# 101_GridPosMainHub.net
KiCad netlist of a schematic drawn in Altium Designer
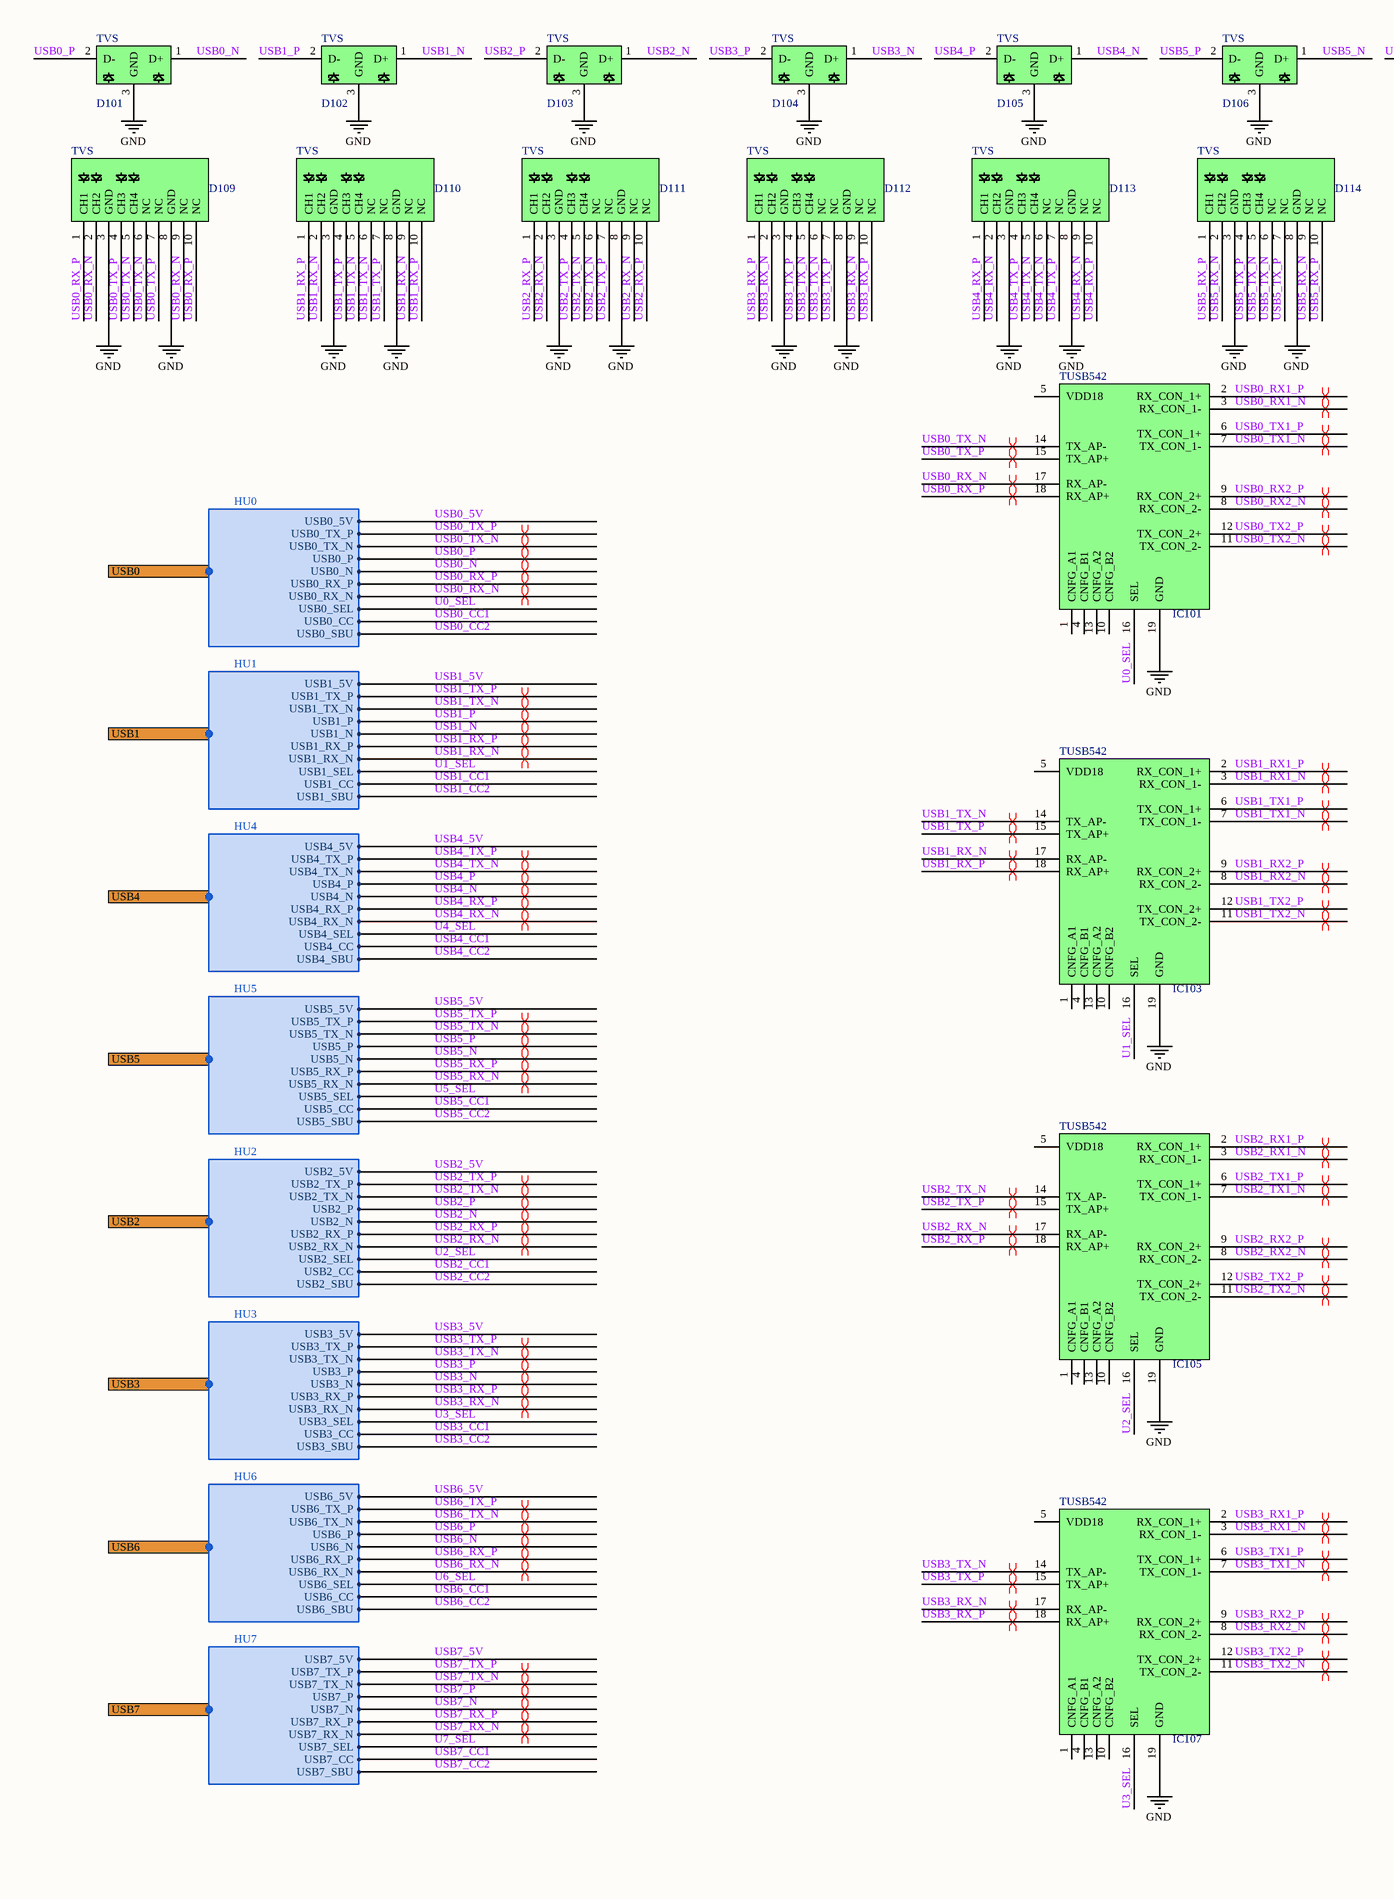
[diagram p0: 101_GridPosMainHub.SchDoc, left]
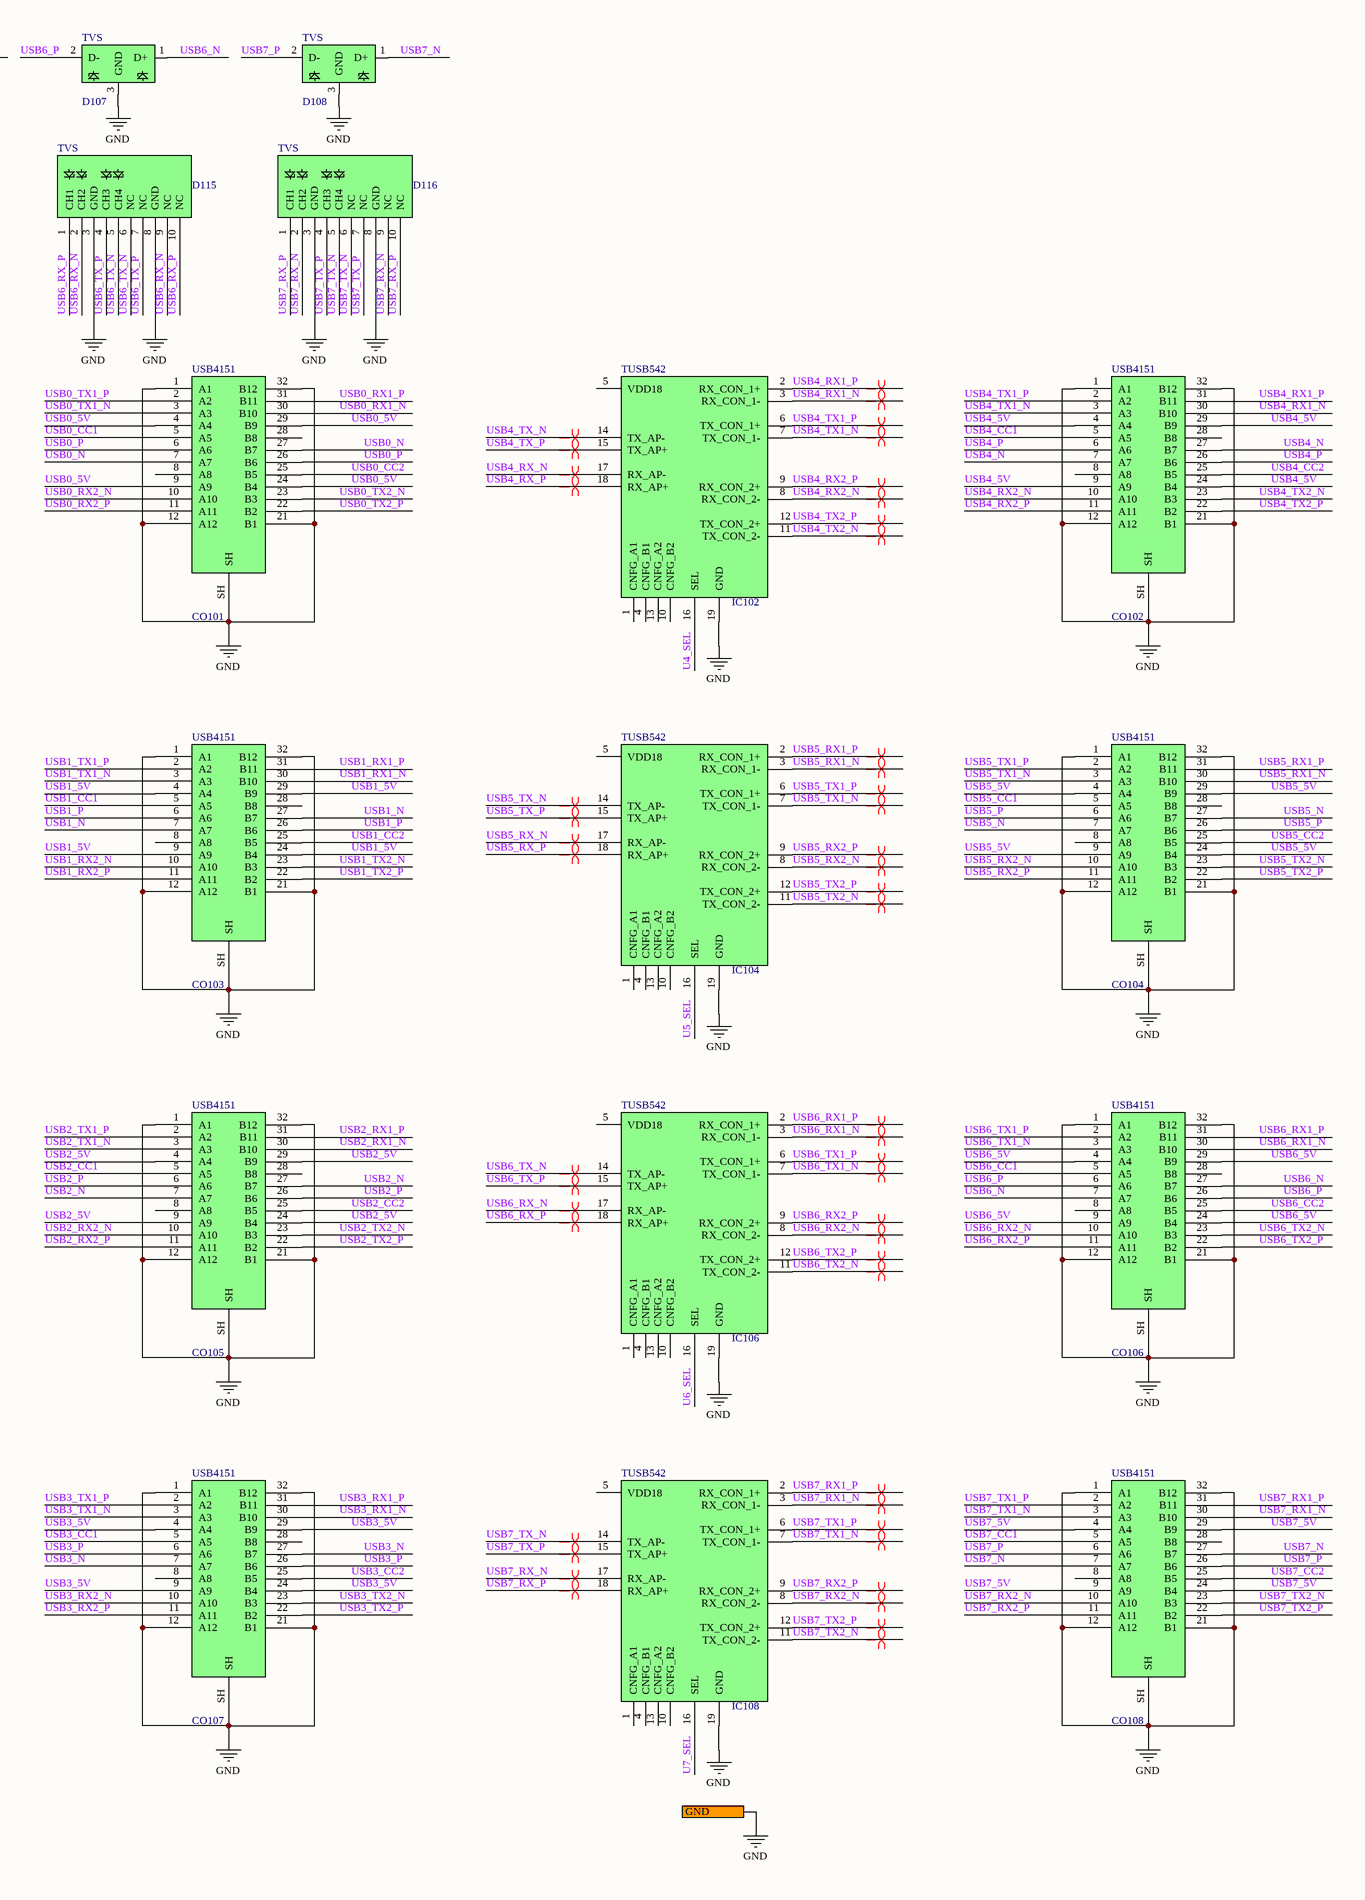
[diagram p1: 101_GridPosMainHub.SchDoc, right]

(export (version "E")
  (design (tool "Eeschema 10.0.6"))
  (components
    (comp (ref "CO101")
      (value "USB4151")
      (footprint "USB4151-GF-C")
      (description "USB C connector Plug Vertical")
      (fields
        (field (name "REFVAL") "USB4151")
        (field (name "PART NUMBER") "CO0017")
        (field (name "MANFACTPART") "USB4151-GF-C")
      )
      (libsource (lib "GTS_Database") (part "USB-CC"))
    )
    (comp (ref "CO102")
      (value "USB4151")
      (footprint "USB4151-GF-C")
      (description "USB C connector Plug Vertical")
      (fields
        (field (name "REFVAL") "USB4151")
        (field (name "PART NUMBER") "CO0017")
        (field (name "MANFACTPART") "USB4151-GF-C")
      )
      (libsource (lib "GTS_Database") (part "USB-CC"))
    )
    (comp (ref "CO103")
      (value "USB4151")
      (footprint "USB4151-GF-C")
      (description "USB C connector Plug Vertical")
      (fields
        (field (name "REFVAL") "USB4151")
        (field (name "PART NUMBER") "CO0017")
        (field (name "MANFACTPART") "USB4151-GF-C")
      )
      (libsource (lib "GTS_Database") (part "USB-CC"))
    )
    (comp (ref "CO104")
      (value "USB4151")
      (footprint "USB4151-GF-C")
      (description "USB C connector Plug Vertical")
      (fields
        (field (name "REFVAL") "USB4151")
        (field (name "PART NUMBER") "CO0017")
        (field (name "MANFACTPART") "USB4151-GF-C")
      )
      (libsource (lib "GTS_Database") (part "USB-CC"))
    )
    (comp (ref "CO105")
      (value "USB4151")
      (footprint "USB4151-GF-C")
      (description "USB C connector Plug Vertical")
      (fields
        (field (name "REFVAL") "USB4151")
        (field (name "PART NUMBER") "CO0017")
        (field (name "MANFACTPART") "USB4151-GF-C")
      )
      (libsource (lib "GTS_Database") (part "USB-CC"))
    )
    (comp (ref "CO106")
      (value "USB4151")
      (footprint "USB4151-GF-C")
      (description "USB C connector Plug Vertical")
      (fields
        (field (name "REFVAL") "USB4151")
        (field (name "PART NUMBER") "CO0017")
        (field (name "MANFACTPART") "USB4151-GF-C")
      )
      (libsource (lib "GTS_Database") (part "USB-CC"))
    )
    (comp (ref "CO107")
      (value "USB4151")
      (footprint "USB4151-GF-C")
      (description "USB C connector Plug Vertical")
      (fields
        (field (name "REFVAL") "USB4151")
        (field (name "PART NUMBER") "CO0017")
        (field (name "MANFACTPART") "USB4151-GF-C")
      )
      (libsource (lib "GTS_Database") (part "USB-CC"))
    )
    (comp (ref "CO108")
      (value "USB4151")
      (footprint "USB4151-GF-C")
      (description "USB C connector Plug Vertical")
      (fields
        (field (name "REFVAL") "USB4151")
        (field (name "PART NUMBER") "CO0017")
        (field (name "MANFACTPART") "USB4151-GF-C")
      )
      (libsource (lib "GTS_Database") (part "USB-CC"))
    )
    (comp (ref "D101")
      (value "TVS")
      (footprint "SOT-3")
      (description "USB 2 TVS Diode")
      (fields
        (field (name "REFVAL") "TVS")
        (field (name "PART NUMBER") "DI0002")
        (field (name "MANFACTPART") "TPD2EUSB30DRTR")
      )
      (libsource (lib "GTS_Database") (part "USB2TVS"))
    )
    (comp (ref "D102")
      (value "TVS")
      (footprint "SOT-3")
      (description "USB 2 TVS Diode")
      (fields
        (field (name "REFVAL") "TVS")
        (field (name "PART NUMBER") "DI0002")
        (field (name "MANFACTPART") "TPD2EUSB30DRTR")
      )
      (libsource (lib "GTS_Database") (part "USB2TVS"))
    )
    (comp (ref "D103")
      (value "TVS")
      (footprint "SOT-3")
      (description "USB 2 TVS Diode")
      (fields
        (field (name "REFVAL") "TVS")
        (field (name "PART NUMBER") "DI0002")
        (field (name "MANFACTPART") "TPD2EUSB30DRTR")
      )
      (libsource (lib "GTS_Database") (part "USB2TVS"))
    )
    (comp (ref "D104")
      (value "TVS")
      (footprint "SOT-3")
      (description "USB 2 TVS Diode")
      (fields
        (field (name "REFVAL") "TVS")
        (field (name "PART NUMBER") "DI0002")
        (field (name "MANFACTPART") "TPD2EUSB30DRTR")
      )
      (libsource (lib "GTS_Database") (part "USB2TVS"))
    )
    (comp (ref "D105")
      (value "TVS")
      (footprint "SOT-3")
      (description "USB 2 TVS Diode")
      (fields
        (field (name "REFVAL") "TVS")
        (field (name "PART NUMBER") "DI0002")
        (field (name "MANFACTPART") "TPD2EUSB30DRTR")
      )
      (libsource (lib "GTS_Database") (part "USB2TVS"))
    )
    (comp (ref "D106")
      (value "TVS")
      (footprint "SOT-3")
      (description "USB 2 TVS Diode")
      (fields
        (field (name "REFVAL") "TVS")
        (field (name "PART NUMBER") "DI0002")
        (field (name "MANFACTPART") "TPD2EUSB30DRTR")
      )
      (libsource (lib "GTS_Database") (part "USB2TVS"))
    )
    (comp (ref "D107")
      (value "TVS")
      (footprint "SOT-3")
      (description "USB 2 TVS Diode")
      (fields
        (field (name "REFVAL") "TVS")
        (field (name "PART NUMBER") "DI0002")
        (field (name "MANFACTPART") "TPD2EUSB30DRTR")
      )
      (libsource (lib "GTS_Database") (part "USB2TVS"))
    )
    (comp (ref "D108")
      (value "TVS")
      (footprint "SOT-3")
      (description "USB 2 TVS Diode")
      (fields
        (field (name "REFVAL") "TVS")
        (field (name "PART NUMBER") "DI0002")
        (field (name "MANFACTPART") "TPD2EUSB30DRTR")
      )
      (libsource (lib "GTS_Database") (part "USB2TVS"))
    )
    (comp (ref "D109")
      (value "TVS")
      (footprint "SOT-1176-1")
      (description "USB 3 TVS Diode")
      (fields
        (field (name "REFVAL") "TVS")
        (field (name "PART NUMBER") "DI0007")
        (field (name "MANFACTPART") "PUSB3FA2Z")
      )
      (libsource (lib "GTS_Database") (part "USB3TVS"))
    )
    (comp (ref "D110")
      (value "TVS")
      (footprint "SOT-1176-1")
      (description "USB 3 TVS Diode")
      (fields
        (field (name "REFVAL") "TVS")
        (field (name "PART NUMBER") "DI0007")
        (field (name "MANFACTPART") "PUSB3FA2Z")
      )
      (libsource (lib "GTS_Database") (part "USB3TVS"))
    )
    (comp (ref "D111")
      (value "TVS")
      (footprint "SOT-1176-1")
      (description "USB 3 TVS Diode")
      (fields
        (field (name "REFVAL") "TVS")
        (field (name "PART NUMBER") "DI0007")
        (field (name "MANFACTPART") "PUSB3FA2Z")
      )
      (libsource (lib "GTS_Database") (part "USB3TVS"))
    )
    (comp (ref "D112")
      (value "TVS")
      (footprint "SOT-1176-1")
      (description "USB 3 TVS Diode")
      (fields
        (field (name "REFVAL") "TVS")
        (field (name "PART NUMBER") "DI0007")
        (field (name "MANFACTPART") "PUSB3FA2Z")
      )
      (libsource (lib "GTS_Database") (part "USB3TVS"))
    )
    (comp (ref "D113")
      (value "TVS")
      (footprint "SOT-1176-1")
      (description "USB 3 TVS Diode")
      (fields
        (field (name "REFVAL") "TVS")
        (field (name "PART NUMBER") "DI0007")
        (field (name "MANFACTPART") "PUSB3FA2Z")
      )
      (libsource (lib "GTS_Database") (part "USB3TVS"))
    )
    (comp (ref "D114")
      (value "TVS")
      (footprint "SOT-1176-1")
      (description "USB 3 TVS Diode")
      (fields
        (field (name "REFVAL") "TVS")
        (field (name "PART NUMBER") "DI0007")
        (field (name "MANFACTPART") "PUSB3FA2Z")
      )
      (libsource (lib "GTS_Database") (part "USB3TVS"))
    )
    (comp (ref "D115")
      (value "TVS")
      (footprint "SOT-1176-1")
      (description "USB 3 TVS Diode")
      (fields
        (field (name "REFVAL") "TVS")
        (field (name "PART NUMBER") "DI0007")
        (field (name "MANFACTPART") "PUSB3FA2Z")
      )
      (libsource (lib "GTS_Database") (part "USB3TVS"))
    )
    (comp (ref "D116")
      (value "TVS")
      (footprint "SOT-1176-1")
      (description "USB 3 TVS Diode")
      (fields
        (field (name "REFVAL") "TVS")
        (field (name "PART NUMBER") "DI0007")
        (field (name "MANFACTPART") "PUSB3FA2Z")
      )
      (libsource (lib "GTS_Database") (part "USB3TVS"))
    )
    (comp (ref "IC101")
      (value "TUSB542")
      (footprint "X2QFN-18")
      (description "TUSB542 USB Type-C 5 Gbps Redriver 2:1 MUX")
      (fields (field (name "REFVAL") "TUSB542") (field (name "PART NUMBER") "IC0039"))
      (libsource (lib "GTS_Database") (part "TUSB542"))
    )
    (comp (ref "IC102")
      (value "TUSB542")
      (footprint "X2QFN-18")
      (description "TUSB542 USB Type-C 5 Gbps Redriver 2:1 MUX")
      (fields (field (name "REFVAL") "TUSB542") (field (name "PART NUMBER") "IC0039"))
      (libsource (lib "GTS_Database") (part "TUSB542"))
    )
    (comp (ref "IC103")
      (value "TUSB542")
      (footprint "X2QFN-18")
      (description "TUSB542 USB Type-C 5 Gbps Redriver 2:1 MUX")
      (fields (field (name "REFVAL") "TUSB542") (field (name "PART NUMBER") "IC0039"))
      (libsource (lib "GTS_Database") (part "TUSB542"))
    )
    (comp (ref "IC104")
      (value "TUSB542")
      (footprint "X2QFN-18")
      (description "TUSB542 USB Type-C 5 Gbps Redriver 2:1 MUX")
      (fields (field (name "REFVAL") "TUSB542") (field (name "PART NUMBER") "IC0039"))
      (libsource (lib "GTS_Database") (part "TUSB542"))
    )
    (comp (ref "IC105")
      (value "TUSB542")
      (footprint "X2QFN-18")
      (description "TUSB542 USB Type-C 5 Gbps Redriver 2:1 MUX")
      (fields (field (name "REFVAL") "TUSB542") (field (name "PART NUMBER") "IC0039"))
      (libsource (lib "GTS_Database") (part "TUSB542"))
    )
    (comp (ref "IC106")
      (value "TUSB542")
      (footprint "X2QFN-18")
      (description "TUSB542 USB Type-C 5 Gbps Redriver 2:1 MUX")
      (fields (field (name "REFVAL") "TUSB542") (field (name "PART NUMBER") "IC0039"))
      (libsource (lib "GTS_Database") (part "TUSB542"))
    )
    (comp (ref "IC107")
      (value "TUSB542")
      (footprint "X2QFN-18")
      (description "TUSB542 USB Type-C 5 Gbps Redriver 2:1 MUX")
      (fields (field (name "REFVAL") "TUSB542") (field (name "PART NUMBER") "IC0039"))
      (libsource (lib "GTS_Database") (part "TUSB542"))
    )
    (comp (ref "IC108")
      (value "TUSB542")
      (footprint "X2QFN-18")
      (description "TUSB542 USB Type-C 5 Gbps Redriver 2:1 MUX")
      (fields (field (name "REFVAL") "TUSB542") (field (name "PART NUMBER") "IC0039"))
      (libsource (lib "GTS_Database") (part "TUSB542"))
    )
  )
  (nets
    (net (code "9") (name "/U0_SEL") (class "Default")
      (node (ref "IC101") (pin "16") (pinfunction "SEL_16") (pintype "passive"))
    )
    (net (code "10") (name "/U1_SEL") (class "Default")
      (node (ref "IC103") (pin "16") (pinfunction "SEL_16") (pintype "passive"))
    )
    (net (code "11") (name "/U2_SEL") (class "Default")
      (node (ref "IC105") (pin "16") (pinfunction "SEL_16") (pintype "passive"))
    )
    (net (code "12") (name "/U3_SEL") (class "Default")
      (node (ref "IC107") (pin "16") (pinfunction "SEL_16") (pintype "passive"))
    )
    (net (code "13") (name "/U4_SEL") (class "Default")
      (node (ref "IC102") (pin "16") (pinfunction "SEL_16") (pintype "passive"))
    )
    (net (code "14") (name "/U5_SEL") (class "Default")
      (node (ref "IC104") (pin "16") (pinfunction "SEL_16") (pintype "passive"))
    )
    (net (code "15") (name "/U6_SEL") (class "Default")
      (node (ref "IC106") (pin "16") (pinfunction "SEL_16") (pintype "passive"))
    )
    (net (code "16") (name "/U7_SEL") (class "Default")
      (node (ref "IC108") (pin "16") (pinfunction "SEL_16") (pintype "passive"))
    )
    (net (code "17") (name "/USB0_5V") (class "Default")
      (node (ref "CO101") (pin "24") (pinfunction "B4_24") (pintype "passive"))
      (node (ref "CO101") (pin "29") (pinfunction "B9_29") (pintype "passive"))
      (node (ref "CO101") (pin "4") (pinfunction "A4_4") (pintype "passive"))
      (node (ref "CO101") (pin "9") (pinfunction "A9_9") (pintype "passive"))
    )
    (net (code "18") (name "/USB0_CC1") (class "Default")
      (node (ref "CO101") (pin "5") (pinfunction "A5_5") (pintype "passive"))
    )
    (net (code "19") (name "/USB0_CC2") (class "Default")
      (node (ref "CO101") (pin "25") (pinfunction "B5_25") (pintype "passive"))
    )
    (net (code "20") (name "/USB0_N") (class "Default")
      (node (ref "CO101") (pin "27") (pinfunction "B7_27") (pintype "passive"))
      (node (ref "CO101") (pin "7") (pinfunction "A7_7") (pintype "passive"))
      (node (ref "D101") (pin "1") (pinfunction "D+_1") (pintype "passive"))
    )
    (net (code "21") (name "/USB0_P") (class "Default")
      (node (ref "CO101") (pin "26") (pinfunction "B6_26") (pintype "passive"))
      (node (ref "CO101") (pin "6") (pinfunction "A6_6") (pintype "passive"))
      (node (ref "D101") (pin "2") (pinfunction "D-_2") (pintype "passive"))
    )
    (net (code "22") (name "/USB0_RX1_N") (class "Default")
      (node (ref "CO101") (pin "30") (pinfunction "B10_30") (pintype "passive"))
      (node (ref "IC101") (pin "3") (pinfunction "RX_CON_1-_3") (pintype "passive"))
    )
    (net (code "23") (name "/USB0_RX1_P") (class "Default")
      (node (ref "CO101") (pin "31") (pinfunction "B11_31") (pintype "passive"))
      (node (ref "IC101") (pin "2") (pinfunction "RX_CON_1+_2") (pintype "passive"))
    )
    (net (code "24") (name "/USB0_RX2_N") (class "Default")
      (node (ref "CO101") (pin "10") (pinfunction "A10_10") (pintype "passive"))
      (node (ref "IC101") (pin "8") (pinfunction "RX_CON_2-_8") (pintype "passive"))
    )
    (net (code "25") (name "/USB0_RX2_P") (class "Default")
      (node (ref "CO101") (pin "11") (pinfunction "A11_11") (pintype "passive"))
      (node (ref "IC101") (pin "9") (pinfunction "RX_CON_2+_9") (pintype "passive"))
    )
    (net (code "26") (name "/USB0_RX_N") (class "Default")
      (node (ref "D109") (pin "2") (pinfunction "CH2_2") (pintype "passive"))
      (node (ref "D109") (pin "9") (pinfunction "NC_9") (pintype "passive"))
      (node (ref "IC101") (pin "17") (pinfunction "RX_AP-_17") (pintype "passive"))
    )
    (net (code "27") (name "/USB0_RX_P") (class "Default")
      (node (ref "D109") (pin "1") (pinfunction "CH1_1") (pintype "passive"))
      (node (ref "D109") (pin "10") (pinfunction "NC_10") (pintype "passive"))
      (node (ref "IC101") (pin "18") (pinfunction "RX_AP+_18") (pintype "passive"))
    )
    (net (code "28") (name "/USB0_TX1_N") (class "Default")
      (node (ref "CO101") (pin "3") (pinfunction "A3_3") (pintype "passive"))
      (node (ref "IC101") (pin "7") (pinfunction "TX_CON_1-_7") (pintype "passive"))
    )
    (net (code "29") (name "/USB0_TX1_P") (class "Default")
      (node (ref "CO101") (pin "2") (pinfunction "A2_2") (pintype "passive"))
      (node (ref "IC101") (pin "6") (pinfunction "TX_CON_1+_6") (pintype "passive"))
    )
    (net (code "30") (name "/USB0_TX2_N") (class "Default")
      (node (ref "CO101") (pin "23") (pinfunction "B3_23") (pintype "passive"))
      (node (ref "IC101") (pin "11") (pinfunction "TX_CON_2-_11") (pintype "passive"))
    )
    (net (code "31") (name "/USB0_TX2_P") (class "Default")
      (node (ref "CO101") (pin "22") (pinfunction "B2_22") (pintype "passive"))
      (node (ref "IC101") (pin "12") (pinfunction "TX_CON_2+_12") (pintype "passive"))
    )
    (net (code "32") (name "/USB0_TX_N") (class "Default")
      (node (ref "D109") (pin "5") (pinfunction "CH4_5") (pintype "passive"))
      (node (ref "D109") (pin "6") (pinfunction "NC_6") (pintype "passive"))
      (node (ref "IC101") (pin "14") (pinfunction "TX_AP-_14") (pintype "passive"))
    )
    (net (code "33") (name "/USB0_TX_P") (class "Default")
      (node (ref "D109") (pin "4") (pinfunction "CH3_4") (pintype "passive"))
      (node (ref "D109") (pin "7") (pinfunction "NC_7") (pintype "passive"))
      (node (ref "IC101") (pin "15") (pinfunction "TX_AP+_15") (pintype "passive"))
    )
    (net (code "34") (name "/USB1_5V") (class "Default")
      (node (ref "CO103") (pin "24") (pinfunction "B4_24") (pintype "passive"))
      (node (ref "CO103") (pin "29") (pinfunction "B9_29") (pintype "passive"))
      (node (ref "CO103") (pin "4") (pinfunction "A4_4") (pintype "passive"))
      (node (ref "CO103") (pin "9") (pinfunction "A9_9") (pintype "passive"))
    )
    (net (code "35") (name "/USB1_CC1") (class "Default")
      (node (ref "CO103") (pin "5") (pinfunction "A5_5") (pintype "passive"))
    )
    (net (code "36") (name "/USB1_CC2") (class "Default")
      (node (ref "CO103") (pin "25") (pinfunction "B5_25") (pintype "passive"))
    )
    (net (code "37") (name "/USB1_N") (class "Default")
      (node (ref "CO103") (pin "27") (pinfunction "B7_27") (pintype "passive"))
      (node (ref "CO103") (pin "7") (pinfunction "A7_7") (pintype "passive"))
      (node (ref "D102") (pin "1") (pinfunction "D+_1") (pintype "passive"))
    )
    (net (code "38") (name "/USB1_P") (class "Default")
      (node (ref "CO103") (pin "26") (pinfunction "B6_26") (pintype "passive"))
      (node (ref "CO103") (pin "6") (pinfunction "A6_6") (pintype "passive"))
      (node (ref "D102") (pin "2") (pinfunction "D-_2") (pintype "passive"))
    )
    (net (code "39") (name "/USB1_RX1_N") (class "Default")
      (node (ref "CO103") (pin "30") (pinfunction "B10_30") (pintype "passive"))
      (node (ref "IC103") (pin "3") (pinfunction "RX_CON_1-_3") (pintype "passive"))
    )
    (net (code "40") (name "/USB1_RX1_P") (class "Default")
      (node (ref "CO103") (pin "31") (pinfunction "B11_31") (pintype "passive"))
      (node (ref "IC103") (pin "2") (pinfunction "RX_CON_1+_2") (pintype "passive"))
    )
    (net (code "41") (name "/USB1_RX2_N") (class "Default")
      (node (ref "CO103") (pin "10") (pinfunction "A10_10") (pintype "passive"))
      (node (ref "IC103") (pin "8") (pinfunction "RX_CON_2-_8") (pintype "passive"))
    )
    (net (code "42") (name "/USB1_RX2_P") (class "Default")
      (node (ref "CO103") (pin "11") (pinfunction "A11_11") (pintype "passive"))
      (node (ref "IC103") (pin "9") (pinfunction "RX_CON_2+_9") (pintype "passive"))
    )
    (net (code "43") (name "/USB1_RX_N") (class "Default")
      (node (ref "D110") (pin "2") (pinfunction "CH2_2") (pintype "passive"))
      (node (ref "D110") (pin "9") (pinfunction "NC_9") (pintype "passive"))
      (node (ref "IC103") (pin "17") (pinfunction "RX_AP-_17") (pintype "passive"))
    )
    (net (code "44") (name "/USB1_RX_P") (class "Default")
      (node (ref "D110") (pin "1") (pinfunction "CH1_1") (pintype "passive"))
      (node (ref "D110") (pin "10") (pinfunction "NC_10") (pintype "passive"))
      (node (ref "IC103") (pin "18") (pinfunction "RX_AP+_18") (pintype "passive"))
    )
    (net (code "45") (name "/USB1_TX1_N") (class "Default")
      (node (ref "CO103") (pin "3") (pinfunction "A3_3") (pintype "passive"))
      (node (ref "IC103") (pin "7") (pinfunction "TX_CON_1-_7") (pintype "passive"))
    )
    (net (code "46") (name "/USB1_TX1_P") (class "Default")
      (node (ref "CO103") (pin "2") (pinfunction "A2_2") (pintype "passive"))
      (node (ref "IC103") (pin "6") (pinfunction "TX_CON_1+_6") (pintype "passive"))
    )
    (net (code "47") (name "/USB1_TX2_N") (class "Default")
      (node (ref "CO103") (pin "23") (pinfunction "B3_23") (pintype "passive"))
      (node (ref "IC103") (pin "11") (pinfunction "TX_CON_2-_11") (pintype "passive"))
    )
    (net (code "48") (name "/USB1_TX2_P") (class "Default")
      (node (ref "CO103") (pin "22") (pinfunction "B2_22") (pintype "passive"))
      (node (ref "IC103") (pin "12") (pinfunction "TX_CON_2+_12") (pintype "passive"))
    )
    (net (code "49") (name "/USB1_TX_N") (class "Default")
      (node (ref "D110") (pin "5") (pinfunction "CH4_5") (pintype "passive"))
      (node (ref "D110") (pin "6") (pinfunction "NC_6") (pintype "passive"))
      (node (ref "IC103") (pin "14") (pinfunction "TX_AP-_14") (pintype "passive"))
    )
    (net (code "50") (name "/USB1_TX_P") (class "Default")
      (node (ref "D110") (pin "4") (pinfunction "CH3_4") (pintype "passive"))
      (node (ref "D110") (pin "7") (pinfunction "NC_7") (pintype "passive"))
      (node (ref "IC103") (pin "15") (pinfunction "TX_AP+_15") (pintype "passive"))
    )
    (net (code "51") (name "/USB2_5V") (class "Default")
      (node (ref "CO105") (pin "24") (pinfunction "B4_24") (pintype "passive"))
      (node (ref "CO105") (pin "29") (pinfunction "B9_29") (pintype "passive"))
      (node (ref "CO105") (pin "4") (pinfunction "A4_4") (pintype "passive"))
      (node (ref "CO105") (pin "9") (pinfunction "A9_9") (pintype "passive"))
    )
    (net (code "52") (name "/USB2_CC1") (class "Default")
      (node (ref "CO105") (pin "5") (pinfunction "A5_5") (pintype "passive"))
    )
    (net (code "53") (name "/USB2_CC2") (class "Default")
      (node (ref "CO105") (pin "25") (pinfunction "B5_25") (pintype "passive"))
    )
    (net (code "54") (name "/USB2_N") (class "Default")
      (node (ref "CO105") (pin "27") (pinfunction "B7_27") (pintype "passive"))
      (node (ref "CO105") (pin "7") (pinfunction "A7_7") (pintype "passive"))
      (node (ref "D103") (pin "1") (pinfunction "D+_1") (pintype "passive"))
    )
    (net (code "55") (name "/USB2_P") (class "Default")
      (node (ref "CO105") (pin "26") (pinfunction "B6_26") (pintype "passive"))
      (node (ref "CO105") (pin "6") (pinfunction "A6_6") (pintype "passive"))
      (node (ref "D103") (pin "2") (pinfunction "D-_2") (pintype "passive"))
    )
    (net (code "56") (name "/USB2_RX1_N") (class "Default")
      (node (ref "CO105") (pin "30") (pinfunction "B10_30") (pintype "passive"))
      (node (ref "IC105") (pin "3") (pinfunction "RX_CON_1-_3") (pintype "passive"))
    )
    (net (code "57") (name "/USB2_RX1_P") (class "Default")
      (node (ref "CO105") (pin "31") (pinfunction "B11_31") (pintype "passive"))
      (node (ref "IC105") (pin "2") (pinfunction "RX_CON_1+_2") (pintype "passive"))
    )
    (net (code "58") (name "/USB2_RX2_N") (class "Default")
      (node (ref "CO105") (pin "10") (pinfunction "A10_10") (pintype "passive"))
      (node (ref "IC105") (pin "8") (pinfunction "RX_CON_2-_8") (pintype "passive"))
    )
    (net (code "59") (name "/USB2_RX2_P") (class "Default")
      (node (ref "CO105") (pin "11") (pinfunction "A11_11") (pintype "passive"))
      (node (ref "IC105") (pin "9") (pinfunction "RX_CON_2+_9") (pintype "passive"))
    )
    (net (code "60") (name "/USB2_RX_N") (class "Default")
      (node (ref "D111") (pin "2") (pinfunction "CH2_2") (pintype "passive"))
      (node (ref "D111") (pin "9") (pinfunction "NC_9") (pintype "passive"))
      (node (ref "IC105") (pin "17") (pinfunction "RX_AP-_17") (pintype "passive"))
    )
    (net (code "61") (name "/USB2_RX_P") (class "Default")
      (node (ref "D111") (pin "1") (pinfunction "CH1_1") (pintype "passive"))
      (node (ref "D111") (pin "10") (pinfunction "NC_10") (pintype "passive"))
      (node (ref "IC105") (pin "18") (pinfunction "RX_AP+_18") (pintype "passive"))
    )
    (net (code "62") (name "/USB2_TX1_N") (class "Default")
      (node (ref "CO105") (pin "3") (pinfunction "A3_3") (pintype "passive"))
      (node (ref "IC105") (pin "7") (pinfunction "TX_CON_1-_7") (pintype "passive"))
    )
    (net (code "63") (name "/USB2_TX1_P") (class "Default")
      (node (ref "CO105") (pin "2") (pinfunction "A2_2") (pintype "passive"))
      (node (ref "IC105") (pin "6") (pinfunction "TX_CON_1+_6") (pintype "passive"))
    )
    (net (code "64") (name "/USB2_TX2_N") (class "Default")
      (node (ref "CO105") (pin "23") (pinfunction "B3_23") (pintype "passive"))
      (node (ref "IC105") (pin "11") (pinfunction "TX_CON_2-_11") (pintype "passive"))
    )
    (net (code "65") (name "/USB2_TX2_P") (class "Default")
      (node (ref "CO105") (pin "22") (pinfunction "B2_22") (pintype "passive"))
      (node (ref "IC105") (pin "12") (pinfunction "TX_CON_2+_12") (pintype "passive"))
    )
    (net (code "66") (name "/USB2_TX_N") (class "Default")
      (node (ref "D111") (pin "5") (pinfunction "CH4_5") (pintype "passive"))
      (node (ref "D111") (pin "6") (pinfunction "NC_6") (pintype "passive"))
      (node (ref "IC105") (pin "14") (pinfunction "TX_AP-_14") (pintype "passive"))
    )
    (net (code "67") (name "/USB2_TX_P") (class "Default")
      (node (ref "D111") (pin "4") (pinfunction "CH3_4") (pintype "passive"))
      (node (ref "D111") (pin "7") (pinfunction "NC_7") (pintype "passive"))
      (node (ref "IC105") (pin "15") (pinfunction "TX_AP+_15") (pintype "passive"))
    )
    (net (code "68") (name "/USB3_5V") (class "Default")
      (node (ref "CO107") (pin "24") (pinfunction "B4_24") (pintype "passive"))
      (node (ref "CO107") (pin "29") (pinfunction "B9_29") (pintype "passive"))
      (node (ref "CO107") (pin "4") (pinfunction "A4_4") (pintype "passive"))
      (node (ref "CO107") (pin "9") (pinfunction "A9_9") (pintype "passive"))
    )
    (net (code "69") (name "/USB3_CC1") (class "Default")
      (node (ref "CO107") (pin "5") (pinfunction "A5_5") (pintype "passive"))
    )
    (net (code "70") (name "/USB3_CC2") (class "Default")
      (node (ref "CO107") (pin "25") (pinfunction "B5_25") (pintype "passive"))
    )
    (net (code "71") (name "/USB3_N") (class "Default")
      (node (ref "CO107") (pin "27") (pinfunction "B7_27") (pintype "passive"))
      (node (ref "CO107") (pin "7") (pinfunction "A7_7") (pintype "passive"))
      (node (ref "D104") (pin "1") (pinfunction "D+_1") (pintype "passive"))
    )
    (net (code "72") (name "/USB3_P") (class "Default")
      (node (ref "CO107") (pin "26") (pinfunction "B6_26") (pintype "passive"))
      (node (ref "CO107") (pin "6") (pinfunction "A6_6") (pintype "passive"))
      (node (ref "D104") (pin "2") (pinfunction "D-_2") (pintype "passive"))
    )
    (net (code "73") (name "/USB3_RX1_N") (class "Default")
      (node (ref "CO107") (pin "30") (pinfunction "B10_30") (pintype "passive"))
      (node (ref "IC107") (pin "3") (pinfunction "RX_CON_1-_3") (pintype "passive"))
    )
    (net (code "74") (name "/USB3_RX1_P") (class "Default")
      (node (ref "CO107") (pin "31") (pinfunction "B11_31") (pintype "passive"))
      (node (ref "IC107") (pin "2") (pinfunction "RX_CON_1+_2") (pintype "passive"))
    )
    (net (code "75") (name "/USB3_RX2_N") (class "Default")
      (node (ref "CO107") (pin "10") (pinfunction "A10_10") (pintype "passive"))
      (node (ref "IC107") (pin "8") (pinfunction "RX_CON_2-_8") (pintype "passive"))
    )
    (net (code "76") (name "/USB3_RX2_P") (class "Default")
      (node (ref "CO107") (pin "11") (pinfunction "A11_11") (pintype "passive"))
      (node (ref "IC107") (pin "9") (pinfunction "RX_CON_2+_9") (pintype "passive"))
    )
    (net (code "77") (name "/USB3_RX_N") (class "Default")
      (node (ref "D112") (pin "2") (pinfunction "CH2_2") (pintype "passive"))
      (node (ref "D112") (pin "9") (pinfunction "NC_9") (pintype "passive"))
      (node (ref "IC107") (pin "17") (pinfunction "RX_AP-_17") (pintype "passive"))
    )
    (net (code "78") (name "/USB3_RX_P") (class "Default")
      (node (ref "D112") (pin "1") (pinfunction "CH1_1") (pintype "passive"))
      (node (ref "D112") (pin "10") (pinfunction "NC_10") (pintype "passive"))
      (node (ref "IC107") (pin "18") (pinfunction "RX_AP+_18") (pintype "passive"))
    )
    (net (code "79") (name "/USB3_TX1_N") (class "Default")
      (node (ref "CO107") (pin "3") (pinfunction "A3_3") (pintype "passive"))
      (node (ref "IC107") (pin "7") (pinfunction "TX_CON_1-_7") (pintype "passive"))
    )
    (net (code "80") (name "/USB3_TX1_P") (class "Default")
      (node (ref "CO107") (pin "2") (pinfunction "A2_2") (pintype "passive"))
      (node (ref "IC107") (pin "6") (pinfunction "TX_CON_1+_6") (pintype "passive"))
    )
    (net (code "81") (name "/USB3_TX2_N") (class "Default")
      (node (ref "CO107") (pin "23") (pinfunction "B3_23") (pintype "passive"))
      (node (ref "IC107") (pin "11") (pinfunction "TX_CON_2-_11") (pintype "passive"))
    )
    (net (code "82") (name "/USB3_TX2_P") (class "Default")
      (node (ref "CO107") (pin "22") (pinfunction "B2_22") (pintype "passive"))
      (node (ref "IC107") (pin "12") (pinfunction "TX_CON_2+_12") (pintype "passive"))
    )
    (net (code "83") (name "/USB3_TX_N") (class "Default")
      (node (ref "D112") (pin "5") (pinfunction "CH4_5") (pintype "passive"))
      (node (ref "D112") (pin "6") (pinfunction "NC_6") (pintype "passive"))
      (node (ref "IC107") (pin "14") (pinfunction "TX_AP-_14") (pintype "passive"))
    )
    (net (code "84") (name "/USB3_TX_P") (class "Default")
      (node (ref "D112") (pin "4") (pinfunction "CH3_4") (pintype "passive"))
      (node (ref "D112") (pin "7") (pinfunction "NC_7") (pintype "passive"))
      (node (ref "IC107") (pin "15") (pinfunction "TX_AP+_15") (pintype "passive"))
    )
    (net (code "85") (name "/USB4_5V") (class "Default")
      (node (ref "CO102") (pin "24") (pinfunction "B4_24") (pintype "passive"))
      (node (ref "CO102") (pin "29") (pinfunction "B9_29") (pintype "passive"))
      (node (ref "CO102") (pin "4") (pinfunction "A4_4") (pintype "passive"))
      (node (ref "CO102") (pin "9") (pinfunction "A9_9") (pintype "passive"))
    )
    (net (code "86") (name "/USB4_CC1") (class "Default")
      (node (ref "CO102") (pin "5") (pinfunction "A5_5") (pintype "passive"))
    )
    (net (code "87") (name "/USB4_CC2") (class "Default")
      (node (ref "CO102") (pin "25") (pinfunction "B5_25") (pintype "passive"))
    )
    (net (code "88") (name "/USB4_N") (class "Default")
      (node (ref "CO102") (pin "27") (pinfunction "B7_27") (pintype "passive"))
      (node (ref "CO102") (pin "7") (pinfunction "A7_7") (pintype "passive"))
      (node (ref "D105") (pin "1") (pinfunction "D+_1") (pintype "passive"))
    )
    (net (code "89") (name "/USB4_P") (class "Default")
      (node (ref "CO102") (pin "26") (pinfunction "B6_26") (pintype "passive"))
      (node (ref "CO102") (pin "6") (pinfunction "A6_6") (pintype "passive"))
      (node (ref "D105") (pin "2") (pinfunction "D-_2") (pintype "passive"))
    )
    (net (code "90") (name "/USB4_RX1_N") (class "Default")
      (node (ref "CO102") (pin "30") (pinfunction "B10_30") (pintype "passive"))
      (node (ref "IC102") (pin "3") (pinfunction "RX_CON_1-_3") (pintype "passive"))
    )
    (net (code "91") (name "/USB4_RX1_P") (class "Default")
      (node (ref "CO102") (pin "31") (pinfunction "B11_31") (pintype "passive"))
      (node (ref "IC102") (pin "2") (pinfunction "RX_CON_1+_2") (pintype "passive"))
    )
    (net (code "92") (name "/USB4_RX2_N") (class "Default")
      (node (ref "CO102") (pin "10") (pinfunction "A10_10") (pintype "passive"))
      (node (ref "IC102") (pin "8") (pinfunction "RX_CON_2-_8") (pintype "passive"))
    )
    (net (code "93") (name "/USB4_RX2_P") (class "Default")
      (node (ref "CO102") (pin "11") (pinfunction "A11_11") (pintype "passive"))
      (node (ref "IC102") (pin "9") (pinfunction "RX_CON_2+_9") (pintype "passive"))
    )
    (net (code "94") (name "/USB4_RX_N") (class "Default")
      (node (ref "D113") (pin "2") (pinfunction "CH2_2") (pintype "passive"))
      (node (ref "D113") (pin "9") (pinfunction "NC_9") (pintype "passive"))
      (node (ref "IC102") (pin "17") (pinfunction "RX_AP-_17") (pintype "passive"))
    )
    (net (code "95") (name "/USB4_RX_P") (class "Default")
      (node (ref "D113") (pin "1") (pinfunction "CH1_1") (pintype "passive"))
      (node (ref "D113") (pin "10") (pinfunction "NC_10") (pintype "passive"))
      (node (ref "IC102") (pin "18") (pinfunction "RX_AP+_18") (pintype "passive"))
    )
    (net (code "96") (name "/USB4_TX1_N") (class "Default")
      (node (ref "CO102") (pin "3") (pinfunction "A3_3") (pintype "passive"))
      (node (ref "IC102") (pin "7") (pinfunction "TX_CON_1-_7") (pintype "passive"))
    )
    (net (code "97") (name "/USB4_TX1_P") (class "Default")
      (node (ref "CO102") (pin "2") (pinfunction "A2_2") (pintype "passive"))
      (node (ref "IC102") (pin "6") (pinfunction "TX_CON_1+_6") (pintype "passive"))
    )
    (net (code "98") (name "/USB4_TX2_N") (class "Default")
      (node (ref "CO102") (pin "23") (pinfunction "B3_23") (pintype "passive"))
      (node (ref "IC102") (pin "11") (pinfunction "TX_CON_2-_11") (pintype "passive"))
    )
    (net (code "99") (name "/USB4_TX2_P") (class "Default")
      (node (ref "CO102") (pin "22") (pinfunction "B2_22") (pintype "passive"))
      (node (ref "IC102") (pin "12") (pinfunction "TX_CON_2+_12") (pintype "passive"))
    )
    (net (code "100") (name "/USB4_TX_N") (class "Default")
      (node (ref "D113") (pin "5") (pinfunction "CH4_5") (pintype "passive"))
      (node (ref "D113") (pin "6") (pinfunction "NC_6") (pintype "passive"))
      (node (ref "IC102") (pin "14") (pinfunction "TX_AP-_14") (pintype "passive"))
    )
    (net (code "101") (name "/USB4_TX_P") (class "Default")
      (node (ref "D113") (pin "4") (pinfunction "CH3_4") (pintype "passive"))
      (node (ref "D113") (pin "7") (pinfunction "NC_7") (pintype "passive"))
      (node (ref "IC102") (pin "15") (pinfunction "TX_AP+_15") (pintype "passive"))
    )
    (net (code "102") (name "/USB5_5V") (class "Default")
      (node (ref "CO104") (pin "24") (pinfunction "B4_24") (pintype "passive"))
      (node (ref "CO104") (pin "29") (pinfunction "B9_29") (pintype "passive"))
      (node (ref "CO104") (pin "4") (pinfunction "A4_4") (pintype "passive"))
      (node (ref "CO104") (pin "9") (pinfunction "A9_9") (pintype "passive"))
    )
    (net (code "103") (name "/USB5_CC1") (class "Default")
      (node (ref "CO104") (pin "5") (pinfunction "A5_5") (pintype "passive"))
    )
    (net (code "104") (name "/USB5_CC2") (class "Default")
      (node (ref "CO104") (pin "25") (pinfunction "B5_25") (pintype "passive"))
    )
    (net (code "105") (name "/USB5_N") (class "Default")
      (node (ref "CO104") (pin "27") (pinfunction "B7_27") (pintype "passive"))
      (node (ref "CO104") (pin "7") (pinfunction "A7_7") (pintype "passive"))
      (node (ref "D106") (pin "1") (pinfunction "D+_1") (pintype "passive"))
    )
    (net (code "106") (name "/USB5_P") (class "Default")
      (node (ref "CO104") (pin "26") (pinfunction "B6_26") (pintype "passive"))
      (node (ref "CO104") (pin "6") (pinfunction "A6_6") (pintype "passive"))
      (node (ref "D106") (pin "2") (pinfunction "D-_2") (pintype "passive"))
    )
    (net (code "107") (name "/USB5_RX1_N") (class "Default")
      (node (ref "CO104") (pin "30") (pinfunction "B10_30") (pintype "passive"))
      (node (ref "IC104") (pin "3") (pinfunction "RX_CON_1-_3") (pintype "passive"))
    )
    (net (code "108") (name "/USB5_RX1_P") (class "Default")
      (node (ref "CO104") (pin "31") (pinfunction "B11_31") (pintype "passive"))
      (node (ref "IC104") (pin "2") (pinfunction "RX_CON_1+_2") (pintype "passive"))
    )
    (net (code "109") (name "/USB5_RX2_N") (class "Default")
      (node (ref "CO104") (pin "10") (pinfunction "A10_10") (pintype "passive"))
      (node (ref "IC104") (pin "8") (pinfunction "RX_CON_2-_8") (pintype "passive"))
    )
    (net (code "110") (name "/USB5_RX2_P") (class "Default")
      (node (ref "CO104") (pin "11") (pinfunction "A11_11") (pintype "passive"))
      (node (ref "IC104") (pin "9") (pinfunction "RX_CON_2+_9") (pintype "passive"))
    )
    (net (code "111") (name "/USB5_RX_N") (class "Default")
      (node (ref "D114") (pin "2") (pinfunction "CH2_2") (pintype "passive"))
      (node (ref "D114") (pin "9") (pinfunction "NC_9") (pintype "passive"))
      (node (ref "IC104") (pin "17") (pinfunction "RX_AP-_17") (pintype "passive"))
    )
    (net (code "112") (name "/USB5_RX_P") (class "Default")
      (node (ref "D114") (pin "1") (pinfunction "CH1_1") (pintype "passive"))
      (node (ref "D114") (pin "10") (pinfunction "NC_10") (pintype "passive"))
      (node (ref "IC104") (pin "18") (pinfunction "RX_AP+_18") (pintype "passive"))
    )
    (net (code "113") (name "/USB5_TX1_N") (class "Default")
      (node (ref "CO104") (pin "3") (pinfunction "A3_3") (pintype "passive"))
      (node (ref "IC104") (pin "7") (pinfunction "TX_CON_1-_7") (pintype "passive"))
    )
    (net (code "114") (name "/USB5_TX1_P") (class "Default")
      (node (ref "CO104") (pin "2") (pinfunction "A2_2") (pintype "passive"))
      (node (ref "IC104") (pin "6") (pinfunction "TX_CON_1+_6") (pintype "passive"))
    )
    (net (code "115") (name "/USB5_TX2_N") (class "Default")
      (node (ref "CO104") (pin "23") (pinfunction "B3_23") (pintype "passive"))
      (node (ref "IC104") (pin "11") (pinfunction "TX_CON_2-_11") (pintype "passive"))
    )
    (net (code "116") (name "/USB5_TX2_P") (class "Default")
      (node (ref "CO104") (pin "22") (pinfunction "B2_22") (pintype "passive"))
      (node (ref "IC104") (pin "12") (pinfunction "TX_CON_2+_12") (pintype "passive"))
    )
    (net (code "117") (name "/USB5_TX_N") (class "Default")
      (node (ref "D114") (pin "5") (pinfunction "CH4_5") (pintype "passive"))
      (node (ref "D114") (pin "6") (pinfunction "NC_6") (pintype "passive"))
      (node (ref "IC104") (pin "14") (pinfunction "TX_AP-_14") (pintype "passive"))
    )
    (net (code "118") (name "/USB5_TX_P") (class "Default")
      (node (ref "D114") (pin "4") (pinfunction "CH3_4") (pintype "passive"))
      (node (ref "D114") (pin "7") (pinfunction "NC_7") (pintype "passive"))
      (node (ref "IC104") (pin "15") (pinfunction "TX_AP+_15") (pintype "passive"))
    )
    (net (code "119") (name "/USB6_5V") (class "Default")
      (node (ref "CO106") (pin "24") (pinfunction "B4_24") (pintype "passive"))
      (node (ref "CO106") (pin "29") (pinfunction "B9_29") (pintype "passive"))
      (node (ref "CO106") (pin "4") (pinfunction "A4_4") (pintype "passive"))
      (node (ref "CO106") (pin "9") (pinfunction "A9_9") (pintype "passive"))
    )
    (net (code "120") (name "/USB6_CC1") (class "Default")
      (node (ref "CO106") (pin "5") (pinfunction "A5_5") (pintype "passive"))
    )
    (net (code "121") (name "/USB6_CC2") (class "Default")
      (node (ref "CO106") (pin "25") (pinfunction "B5_25") (pintype "passive"))
    )
    (net (code "122") (name "/USB6_N") (class "Default")
      (node (ref "CO106") (pin "27") (pinfunction "B7_27") (pintype "passive"))
      (node (ref "CO106") (pin "7") (pinfunction "A7_7") (pintype "passive"))
      (node (ref "D107") (pin "1") (pinfunction "D+_1") (pintype "passive"))
    )
    (net (code "123") (name "/USB6_P") (class "Default")
      (node (ref "CO106") (pin "26") (pinfunction "B6_26") (pintype "passive"))
      (node (ref "CO106") (pin "6") (pinfunction "A6_6") (pintype "passive"))
      (node (ref "D107") (pin "2") (pinfunction "D-_2") (pintype "passive"))
    )
    (net (code "124") (name "/USB6_RX1_N") (class "Default")
      (node (ref "CO106") (pin "30") (pinfunction "B10_30") (pintype "passive"))
      (node (ref "IC106") (pin "3") (pinfunction "RX_CON_1-_3") (pintype "passive"))
    )
    (net (code "125") (name "/USB6_RX1_P") (class "Default")
      (node (ref "CO106") (pin "31") (pinfunction "B11_31") (pintype "passive"))
      (node (ref "IC106") (pin "2") (pinfunction "RX_CON_1+_2") (pintype "passive"))
    )
    (net (code "126") (name "/USB6_RX2_N") (class "Default")
      (node (ref "CO106") (pin "10") (pinfunction "A10_10") (pintype "passive"))
      (node (ref "IC106") (pin "8") (pinfunction "RX_CON_2-_8") (pintype "passive"))
    )
    (net (code "127") (name "/USB6_RX2_P") (class "Default")
      (node (ref "CO106") (pin "11") (pinfunction "A11_11") (pintype "passive"))
      (node (ref "IC106") (pin "9") (pinfunction "RX_CON_2+_9") (pintype "passive"))
    )
    (net (code "128") (name "/USB6_RX_N") (class "Default")
      (node (ref "D115") (pin "2") (pinfunction "CH2_2") (pintype "passive"))
      (node (ref "D115") (pin "9") (pinfunction "NC_9") (pintype "passive"))
      (node (ref "IC106") (pin "17") (pinfunction "RX_AP-_17") (pintype "passive"))
    )
    (net (code "129") (name "/USB6_RX_P") (class "Default")
      (node (ref "D115") (pin "1") (pinfunction "CH1_1") (pintype "passive"))
      (node (ref "D115") (pin "10") (pinfunction "NC_10") (pintype "passive"))
      (node (ref "IC106") (pin "18") (pinfunction "RX_AP+_18") (pintype "passive"))
    )
    (net (code "130") (name "/USB6_TX1_N") (class "Default")
      (node (ref "CO106") (pin "3") (pinfunction "A3_3") (pintype "passive"))
      (node (ref "IC106") (pin "7") (pinfunction "TX_CON_1-_7") (pintype "passive"))
    )
    (net (code "131") (name "/USB6_TX1_P") (class "Default")
      (node (ref "CO106") (pin "2") (pinfunction "A2_2") (pintype "passive"))
      (node (ref "IC106") (pin "6") (pinfunction "TX_CON_1+_6") (pintype "passive"))
    )
    (net (code "132") (name "/USB6_TX2_N") (class "Default")
      (node (ref "CO106") (pin "23") (pinfunction "B3_23") (pintype "passive"))
      (node (ref "IC106") (pin "11") (pinfunction "TX_CON_2-_11") (pintype "passive"))
    )
    (net (code "133") (name "/USB6_TX2_P") (class "Default")
      (node (ref "CO106") (pin "22") (pinfunction "B2_22") (pintype "passive"))
      (node (ref "IC106") (pin "12") (pinfunction "TX_CON_2+_12") (pintype "passive"))
    )
    (net (code "134") (name "/USB6_TX_N") (class "Default")
      (node (ref "D115") (pin "5") (pinfunction "CH4_5") (pintype "passive"))
      (node (ref "D115") (pin "6") (pinfunction "NC_6") (pintype "passive"))
      (node (ref "IC106") (pin "14") (pinfunction "TX_AP-_14") (pintype "passive"))
    )
    (net (code "135") (name "/USB6_TX_P") (class "Default")
      (node (ref "D115") (pin "4") (pinfunction "CH3_4") (pintype "passive"))
      (node (ref "D115") (pin "7") (pinfunction "NC_7") (pintype "passive"))
      (node (ref "IC106") (pin "15") (pinfunction "TX_AP+_15") (pintype "passive"))
    )
    (net (code "136") (name "/USB7_5V") (class "Default")
      (node (ref "CO108") (pin "24") (pinfunction "B4_24") (pintype "passive"))
      (node (ref "CO108") (pin "29") (pinfunction "B9_29") (pintype "passive"))
      (node (ref "CO108") (pin "4") (pinfunction "A4_4") (pintype "passive"))
      (node (ref "CO108") (pin "9") (pinfunction "A9_9") (pintype "passive"))
    )
    (net (code "137") (name "/USB7_CC1") (class "Default")
      (node (ref "CO108") (pin "5") (pinfunction "A5_5") (pintype "passive"))
    )
    (net (code "138") (name "/USB7_CC2") (class "Default")
      (node (ref "CO108") (pin "25") (pinfunction "B5_25") (pintype "passive"))
    )
    (net (code "139") (name "/USB7_N") (class "Default")
      (node (ref "CO108") (pin "27") (pinfunction "B7_27") (pintype "passive"))
      (node (ref "CO108") (pin "7") (pinfunction "A7_7") (pintype "passive"))
      (node (ref "D108") (pin "1") (pinfunction "D+_1") (pintype "passive"))
    )
    (net (code "140") (name "/USB7_P") (class "Default")
      (node (ref "CO108") (pin "26") (pinfunction "B6_26") (pintype "passive"))
      (node (ref "CO108") (pin "6") (pinfunction "A6_6") (pintype "passive"))
      (node (ref "D108") (pin "2") (pinfunction "D-_2") (pintype "passive"))
    )
    (net (code "141") (name "/USB7_RX1_N") (class "Default")
      (node (ref "CO108") (pin "30") (pinfunction "B10_30") (pintype "passive"))
      (node (ref "IC108") (pin "3") (pinfunction "RX_CON_1-_3") (pintype "passive"))
    )
    (net (code "142") (name "/USB7_RX1_P") (class "Default")
      (node (ref "CO108") (pin "31") (pinfunction "B11_31") (pintype "passive"))
      (node (ref "IC108") (pin "2") (pinfunction "RX_CON_1+_2") (pintype "passive"))
    )
    (net (code "143") (name "/USB7_RX2_N") (class "Default")
      (node (ref "CO108") (pin "10") (pinfunction "A10_10") (pintype "passive"))
      (node (ref "IC108") (pin "8") (pinfunction "RX_CON_2-_8") (pintype "passive"))
    )
    (net (code "144") (name "/USB7_RX2_P") (class "Default")
      (node (ref "CO108") (pin "11") (pinfunction "A11_11") (pintype "passive"))
      (node (ref "IC108") (pin "9") (pinfunction "RX_CON_2+_9") (pintype "passive"))
    )
    (net (code "145") (name "/USB7_RX_N") (class "Default")
      (node (ref "D116") (pin "2") (pinfunction "CH2_2") (pintype "passive"))
      (node (ref "D116") (pin "9") (pinfunction "NC_9") (pintype "passive"))
      (node (ref "IC108") (pin "17") (pinfunction "RX_AP-_17") (pintype "passive"))
    )
    (net (code "146") (name "/USB7_RX_P") (class "Default")
      (node (ref "D116") (pin "1") (pinfunction "CH1_1") (pintype "passive"))
      (node (ref "D116") (pin "10") (pinfunction "NC_10") (pintype "passive"))
      (node (ref "IC108") (pin "18") (pinfunction "RX_AP+_18") (pintype "passive"))
    )
    (net (code "147") (name "/USB7_TX1_N") (class "Default")
      (node (ref "CO108") (pin "3") (pinfunction "A3_3") (pintype "passive"))
      (node (ref "IC108") (pin "7") (pinfunction "TX_CON_1-_7") (pintype "passive"))
    )
    (net (code "148") (name "/USB7_TX1_P") (class "Default")
      (node (ref "CO108") (pin "2") (pinfunction "A2_2") (pintype "passive"))
      (node (ref "IC108") (pin "6") (pinfunction "TX_CON_1+_6") (pintype "passive"))
    )
    (net (code "149") (name "/USB7_TX2_N") (class "Default")
      (node (ref "CO108") (pin "23") (pinfunction "B3_23") (pintype "passive"))
      (node (ref "IC108") (pin "11") (pinfunction "TX_CON_2-_11") (pintype "passive"))
    )
    (net (code "150") (name "/USB7_TX2_P") (class "Default")
      (node (ref "CO108") (pin "22") (pinfunction "B2_22") (pintype "passive"))
      (node (ref "IC108") (pin "12") (pinfunction "TX_CON_2+_12") (pintype "passive"))
    )
    (net (code "151") (name "/USB7_TX_N") (class "Default")
      (node (ref "D116") (pin "5") (pinfunction "CH4_5") (pintype "passive"))
      (node (ref "D116") (pin "6") (pinfunction "NC_6") (pintype "passive"))
      (node (ref "IC108") (pin "14") (pinfunction "TX_AP-_14") (pintype "passive"))
    )
    (net (code "152") (name "/USB7_TX_P") (class "Default")
      (node (ref "D116") (pin "4") (pinfunction "CH3_4") (pintype "passive"))
      (node (ref "D116") (pin "7") (pinfunction "NC_7") (pintype "passive"))
      (node (ref "IC108") (pin "15") (pinfunction "TX_AP+_15") (pintype "passive"))
    )
    (net (code "161") (name "GND") (class "Default")
      (node (ref "CO101") (pin "1") (pinfunction "A1_1") (pintype "passive"))
      (node (ref "CO101") (pin "12") (pinfunction "A12_12") (pintype "passive"))
      (node (ref "CO101") (pin "21") (pinfunction "B1_21") (pintype "passive"))
      (node (ref "CO101") (pin "32") (pinfunction "B12_32") (pintype "passive"))
      (node (ref "CO101") (pin "SH") (pinfunction "SH_SH") (pintype "power_in"))
      (node (ref "CO102") (pin "1") (pinfunction "A1_1") (pintype "passive"))
      (node (ref "CO102") (pin "12") (pinfunction "A12_12") (pintype "passive"))
      (node (ref "CO102") (pin "21") (pinfunction "B1_21") (pintype "passive"))
      (node (ref "CO102") (pin "32") (pinfunction "B12_32") (pintype "passive"))
      (node (ref "CO102") (pin "SH") (pinfunction "SH_SH") (pintype "power_in"))
      (node (ref "CO103") (pin "1") (pinfunction "A1_1") (pintype "passive"))
      (node (ref "CO103") (pin "12") (pinfunction "A12_12") (pintype "passive"))
      (node (ref "CO103") (pin "21") (pinfunction "B1_21") (pintype "passive"))
      (node (ref "CO103") (pin "32") (pinfunction "B12_32") (pintype "passive"))
      (node (ref "CO103") (pin "SH") (pinfunction "SH_SH") (pintype "power_in"))
      (node (ref "CO104") (pin "1") (pinfunction "A1_1") (pintype "passive"))
      (node (ref "CO104") (pin "12") (pinfunction "A12_12") (pintype "passive"))
      (node (ref "CO104") (pin "21") (pinfunction "B1_21") (pintype "passive"))
      (node (ref "CO104") (pin "32") (pinfunction "B12_32") (pintype "passive"))
      (node (ref "CO104") (pin "SH") (pinfunction "SH_SH") (pintype "power_in"))
      (node (ref "CO105") (pin "1") (pinfunction "A1_1") (pintype "passive"))
      (node (ref "CO105") (pin "12") (pinfunction "A12_12") (pintype "passive"))
      (node (ref "CO105") (pin "21") (pinfunction "B1_21") (pintype "passive"))
      (node (ref "CO105") (pin "32") (pinfunction "B12_32") (pintype "passive"))
      (node (ref "CO105") (pin "SH") (pinfunction "SH_SH") (pintype "power_in"))
      (node (ref "CO106") (pin "1") (pinfunction "A1_1") (pintype "passive"))
      (node (ref "CO106") (pin "12") (pinfunction "A12_12") (pintype "passive"))
      (node (ref "CO106") (pin "21") (pinfunction "B1_21") (pintype "passive"))
      (node (ref "CO106") (pin "32") (pinfunction "B12_32") (pintype "passive"))
      (node (ref "CO106") (pin "SH") (pinfunction "SH_SH") (pintype "power_in"))
      (node (ref "CO107") (pin "1") (pinfunction "A1_1") (pintype "passive"))
      (node (ref "CO107") (pin "12") (pinfunction "A12_12") (pintype "passive"))
      (node (ref "CO107") (pin "21") (pinfunction "B1_21") (pintype "passive"))
      (node (ref "CO107") (pin "32") (pinfunction "B12_32") (pintype "passive"))
      (node (ref "CO107") (pin "SH") (pinfunction "SH_SH") (pintype "power_in"))
      (node (ref "CO108") (pin "1") (pinfunction "A1_1") (pintype "passive"))
      (node (ref "CO108") (pin "12") (pinfunction "A12_12") (pintype "passive"))
      (node (ref "CO108") (pin "21") (pinfunction "B1_21") (pintype "passive"))
      (node (ref "CO108") (pin "32") (pinfunction "B12_32") (pintype "passive"))
      (node (ref "CO108") (pin "SH") (pinfunction "SH_SH") (pintype "power_in"))
      (node (ref "D101") (pin "3") (pinfunction "GND_3") (pintype "power_in"))
      (node (ref "D102") (pin "3") (pinfunction "GND_3") (pintype "power_in"))
      (node (ref "D103") (pin "3") (pinfunction "GND_3") (pintype "power_in"))
      (node (ref "D104") (pin "3") (pinfunction "GND_3") (pintype "power_in"))
      (node (ref "D105") (pin "3") (pinfunction "GND_3") (pintype "power_in"))
      (node (ref "D106") (pin "3") (pinfunction "GND_3") (pintype "power_in"))
      (node (ref "D107") (pin "3") (pinfunction "GND_3") (pintype "power_in"))
      (node (ref "D108") (pin "3") (pinfunction "GND_3") (pintype "power_in"))
      (node (ref "D109") (pin "3") (pinfunction "GND_3") (pintype "passive"))
      (node (ref "D109") (pin "8") (pinfunction "GND_8") (pintype "passive"))
      (node (ref "D110") (pin "3") (pinfunction "GND_3") (pintype "passive"))
      (node (ref "D110") (pin "8") (pinfunction "GND_8") (pintype "passive"))
      (node (ref "D111") (pin "3") (pinfunction "GND_3") (pintype "passive"))
      (node (ref "D111") (pin "8") (pinfunction "GND_8") (pintype "passive"))
      (node (ref "D112") (pin "3") (pinfunction "GND_3") (pintype "passive"))
      (node (ref "D112") (pin "8") (pinfunction "GND_8") (pintype "passive"))
      (node (ref "D113") (pin "3") (pinfunction "GND_3") (pintype "passive"))
      (node (ref "D113") (pin "8") (pinfunction "GND_8") (pintype "passive"))
      (node (ref "D114") (pin "3") (pinfunction "GND_3") (pintype "passive"))
      (node (ref "D114") (pin "8") (pinfunction "GND_8") (pintype "passive"))
      (node (ref "D115") (pin "3") (pinfunction "GND_3") (pintype "passive"))
      (node (ref "D115") (pin "8") (pinfunction "GND_8") (pintype "passive"))
      (node (ref "D116") (pin "3") (pinfunction "GND_3") (pintype "passive"))
      (node (ref "D116") (pin "8") (pinfunction "GND_8") (pintype "passive"))
      (node (ref "IC101") (pin "19") (pinfunction "GND_19") (pintype "passive"))
      (node (ref "IC102") (pin "19") (pinfunction "GND_19") (pintype "passive"))
      (node (ref "IC103") (pin "19") (pinfunction "GND_19") (pintype "passive"))
      (node (ref "IC104") (pin "19") (pinfunction "GND_19") (pintype "passive"))
      (node (ref "IC105") (pin "19") (pinfunction "GND_19") (pintype "passive"))
      (node (ref "IC106") (pin "19") (pinfunction "GND_19") (pintype "passive"))
      (node (ref "IC107") (pin "19") (pinfunction "GND_19") (pintype "passive"))
      (node (ref "IC108") (pin "19") (pinfunction "GND_19") (pintype "passive"))
    )
    (net (code "162") (name "unconnected-(CO101-A8-Pad8)") (class "Default")
      (node (ref "CO101") (pin "8") (pinfunction "A8_8") (pintype "passive"))
    )
    (net (code "163") (name "unconnected-(CO101-B8-Pad28)") (class "Default")
      (node (ref "CO101") (pin "28") (pinfunction "B8_28") (pintype "passive"))
    )
    (net (code "164") (name "unconnected-(CO102-A8-Pad8)") (class "Default")
      (node (ref "CO102") (pin "8") (pinfunction "A8_8") (pintype "passive"))
    )
    (net (code "165") (name "unconnected-(CO102-B8-Pad28)") (class "Default")
      (node (ref "CO102") (pin "28") (pinfunction "B8_28") (pintype "passive"))
    )
    (net (code "166") (name "unconnected-(CO103-A8-Pad8)") (class "Default")
      (node (ref "CO103") (pin "8") (pinfunction "A8_8") (pintype "passive"))
    )
    (net (code "167") (name "unconnected-(CO103-B8-Pad28)") (class "Default")
      (node (ref "CO103") (pin "28") (pinfunction "B8_28") (pintype "passive"))
    )
    (net (code "168") (name "unconnected-(CO104-A8-Pad8)") (class "Default")
      (node (ref "CO104") (pin "8") (pinfunction "A8_8") (pintype "passive"))
    )
    (net (code "169") (name "unconnected-(CO104-B8-Pad28)") (class "Default")
      (node (ref "CO104") (pin "28") (pinfunction "B8_28") (pintype "passive"))
    )
    (net (code "170") (name "unconnected-(CO105-A8-Pad8)") (class "Default")
      (node (ref "CO105") (pin "8") (pinfunction "A8_8") (pintype "passive"))
    )
    (net (code "171") (name "unconnected-(CO105-B8-Pad28)") (class "Default")
      (node (ref "CO105") (pin "28") (pinfunction "B8_28") (pintype "passive"))
    )
    (net (code "172") (name "unconnected-(CO106-A8-Pad8)") (class "Default")
      (node (ref "CO106") (pin "8") (pinfunction "A8_8") (pintype "passive"))
    )
    (net (code "173") (name "unconnected-(CO106-B8-Pad28)") (class "Default")
      (node (ref "CO106") (pin "28") (pinfunction "B8_28") (pintype "passive"))
    )
    (net (code "174") (name "unconnected-(CO107-A8-Pad8)") (class "Default")
      (node (ref "CO107") (pin "8") (pinfunction "A8_8") (pintype "passive"))
    )
    (net (code "175") (name "unconnected-(CO107-B8-Pad28)") (class "Default")
      (node (ref "CO107") (pin "28") (pinfunction "B8_28") (pintype "passive"))
    )
    (net (code "176") (name "unconnected-(CO108-A8-Pad8)") (class "Default")
      (node (ref "CO108") (pin "8") (pinfunction "A8_8") (pintype "passive"))
    )
    (net (code "177") (name "unconnected-(CO108-B8-Pad28)") (class "Default")
      (node (ref "CO108") (pin "28") (pinfunction "B8_28") (pintype "passive"))
    )
    (net (code "178") (name "unconnected-(IC101-CNFG_A1-Pad1)") (class "Default")
      (node (ref "IC101") (pin "1") (pinfunction "CNFG_A1_1") (pintype "passive"))
    )
    (net (code "179") (name "unconnected-(IC101-CNFG_A2-Pad13)") (class "Default")
      (node (ref "IC101") (pin "13") (pinfunction "CNFG_A2_13") (pintype "passive"))
    )
    (net (code "180") (name "unconnected-(IC101-CNFG_B1-Pad4)") (class "Default")
      (node (ref "IC101") (pin "4") (pinfunction "CNFG_B1_4") (pintype "passive"))
    )
    (net (code "181") (name "unconnected-(IC101-CNFG_B2-Pad10)") (class "Default")
      (node (ref "IC101") (pin "10") (pinfunction "CNFG_B2_10") (pintype "passive"))
    )
    (net (code "182") (name "unconnected-(IC101-VDD18-Pad5)") (class "Default")
      (node (ref "IC101") (pin "5") (pinfunction "VDD18_5") (pintype "passive"))
    )
    (net (code "183") (name "unconnected-(IC102-CNFG_A1-Pad1)") (class "Default")
      (node (ref "IC102") (pin "1") (pinfunction "CNFG_A1_1") (pintype "passive"))
    )
    (net (code "184") (name "unconnected-(IC102-CNFG_A2-Pad13)") (class "Default")
      (node (ref "IC102") (pin "13") (pinfunction "CNFG_A2_13") (pintype "passive"))
    )
    (net (code "185") (name "unconnected-(IC102-CNFG_B1-Pad4)") (class "Default")
      (node (ref "IC102") (pin "4") (pinfunction "CNFG_B1_4") (pintype "passive"))
    )
    (net (code "186") (name "unconnected-(IC102-CNFG_B2-Pad10)") (class "Default")
      (node (ref "IC102") (pin "10") (pinfunction "CNFG_B2_10") (pintype "passive"))
    )
    (net (code "187") (name "unconnected-(IC102-VDD18-Pad5)") (class "Default")
      (node (ref "IC102") (pin "5") (pinfunction "VDD18_5") (pintype "passive"))
    )
    (net (code "188") (name "unconnected-(IC103-CNFG_A1-Pad1)") (class "Default")
      (node (ref "IC103") (pin "1") (pinfunction "CNFG_A1_1") (pintype "passive"))
    )
    (net (code "189") (name "unconnected-(IC103-CNFG_A2-Pad13)") (class "Default")
      (node (ref "IC103") (pin "13") (pinfunction "CNFG_A2_13") (pintype "passive"))
    )
    (net (code "190") (name "unconnected-(IC103-CNFG_B1-Pad4)") (class "Default")
      (node (ref "IC103") (pin "4") (pinfunction "CNFG_B1_4") (pintype "passive"))
    )
    (net (code "191") (name "unconnected-(IC103-CNFG_B2-Pad10)") (class "Default")
      (node (ref "IC103") (pin "10") (pinfunction "CNFG_B2_10") (pintype "passive"))
    )
    (net (code "192") (name "unconnected-(IC103-VDD18-Pad5)") (class "Default")
      (node (ref "IC103") (pin "5") (pinfunction "VDD18_5") (pintype "passive"))
    )
    (net (code "193") (name "unconnected-(IC104-CNFG_A1-Pad1)") (class "Default")
      (node (ref "IC104") (pin "1") (pinfunction "CNFG_A1_1") (pintype "passive"))
    )
    (net (code "194") (name "unconnected-(IC104-CNFG_A2-Pad13)") (class "Default")
      (node (ref "IC104") (pin "13") (pinfunction "CNFG_A2_13") (pintype "passive"))
    )
    (net (code "195") (name "unconnected-(IC104-CNFG_B1-Pad4)") (class "Default")
      (node (ref "IC104") (pin "4") (pinfunction "CNFG_B1_4") (pintype "passive"))
    )
    (net (code "196") (name "unconnected-(IC104-CNFG_B2-Pad10)") (class "Default")
      (node (ref "IC104") (pin "10") (pinfunction "CNFG_B2_10") (pintype "passive"))
    )
    (net (code "197") (name "unconnected-(IC104-VDD18-Pad5)") (class "Default")
      (node (ref "IC104") (pin "5") (pinfunction "VDD18_5") (pintype "passive"))
    )
    (net (code "198") (name "unconnected-(IC105-CNFG_A1-Pad1)") (class "Default")
      (node (ref "IC105") (pin "1") (pinfunction "CNFG_A1_1") (pintype "passive"))
    )
    (net (code "199") (name "unconnected-(IC105-CNFG_A2-Pad13)") (class "Default")
      (node (ref "IC105") (pin "13") (pinfunction "CNFG_A2_13") (pintype "passive"))
    )
    (net (code "200") (name "unconnected-(IC105-CNFG_B1-Pad4)") (class "Default")
      (node (ref "IC105") (pin "4") (pinfunction "CNFG_B1_4") (pintype "passive"))
    )
    (net (code "201") (name "unconnected-(IC105-CNFG_B2-Pad10)") (class "Default")
      (node (ref "IC105") (pin "10") (pinfunction "CNFG_B2_10") (pintype "passive"))
    )
    (net (code "202") (name "unconnected-(IC105-VDD18-Pad5)") (class "Default")
      (node (ref "IC105") (pin "5") (pinfunction "VDD18_5") (pintype "passive"))
    )
    (net (code "203") (name "unconnected-(IC106-CNFG_A1-Pad1)") (class "Default")
      (node (ref "IC106") (pin "1") (pinfunction "CNFG_A1_1") (pintype "passive"))
    )
    (net (code "204") (name "unconnected-(IC106-CNFG_A2-Pad13)") (class "Default")
      (node (ref "IC106") (pin "13") (pinfunction "CNFG_A2_13") (pintype "passive"))
    )
    (net (code "205") (name "unconnected-(IC106-CNFG_B1-Pad4)") (class "Default")
      (node (ref "IC106") (pin "4") (pinfunction "CNFG_B1_4") (pintype "passive"))
    )
    (net (code "206") (name "unconnected-(IC106-CNFG_B2-Pad10)") (class "Default")
      (node (ref "IC106") (pin "10") (pinfunction "CNFG_B2_10") (pintype "passive"))
    )
    (net (code "207") (name "unconnected-(IC106-VDD18-Pad5)") (class "Default")
      (node (ref "IC106") (pin "5") (pinfunction "VDD18_5") (pintype "passive"))
    )
    (net (code "208") (name "unconnected-(IC107-CNFG_A1-Pad1)") (class "Default")
      (node (ref "IC107") (pin "1") (pinfunction "CNFG_A1_1") (pintype "passive"))
    )
    (net (code "209") (name "unconnected-(IC107-CNFG_A2-Pad13)") (class "Default")
      (node (ref "IC107") (pin "13") (pinfunction "CNFG_A2_13") (pintype "passive"))
    )
    (net (code "210") (name "unconnected-(IC107-CNFG_B1-Pad4)") (class "Default")
      (node (ref "IC107") (pin "4") (pinfunction "CNFG_B1_4") (pintype "passive"))
    )
    (net (code "211") (name "unconnected-(IC107-CNFG_B2-Pad10)") (class "Default")
      (node (ref "IC107") (pin "10") (pinfunction "CNFG_B2_10") (pintype "passive"))
    )
    (net (code "212") (name "unconnected-(IC107-VDD18-Pad5)") (class "Default")
      (node (ref "IC107") (pin "5") (pinfunction "VDD18_5") (pintype "passive"))
    )
    (net (code "213") (name "unconnected-(IC108-CNFG_A1-Pad1)") (class "Default")
      (node (ref "IC108") (pin "1") (pinfunction "CNFG_A1_1") (pintype "passive"))
    )
    (net (code "214") (name "unconnected-(IC108-CNFG_A2-Pad13)") (class "Default")
      (node (ref "IC108") (pin "13") (pinfunction "CNFG_A2_13") (pintype "passive"))
    )
    (net (code "215") (name "unconnected-(IC108-CNFG_B1-Pad4)") (class "Default")
      (node (ref "IC108") (pin "4") (pinfunction "CNFG_B1_4") (pintype "passive"))
    )
    (net (code "216") (name "unconnected-(IC108-CNFG_B2-Pad10)") (class "Default")
      (node (ref "IC108") (pin "10") (pinfunction "CNFG_B2_10") (pintype "passive"))
    )
    (net (code "217") (name "unconnected-(IC108-VDD18-Pad5)") (class "Default")
      (node (ref "IC108") (pin "5") (pinfunction "VDD18_5") (pintype "passive"))
    )
  )
)
